# MegaBotv2.net
KiCad netlist of a schematic drawn in EAGLE
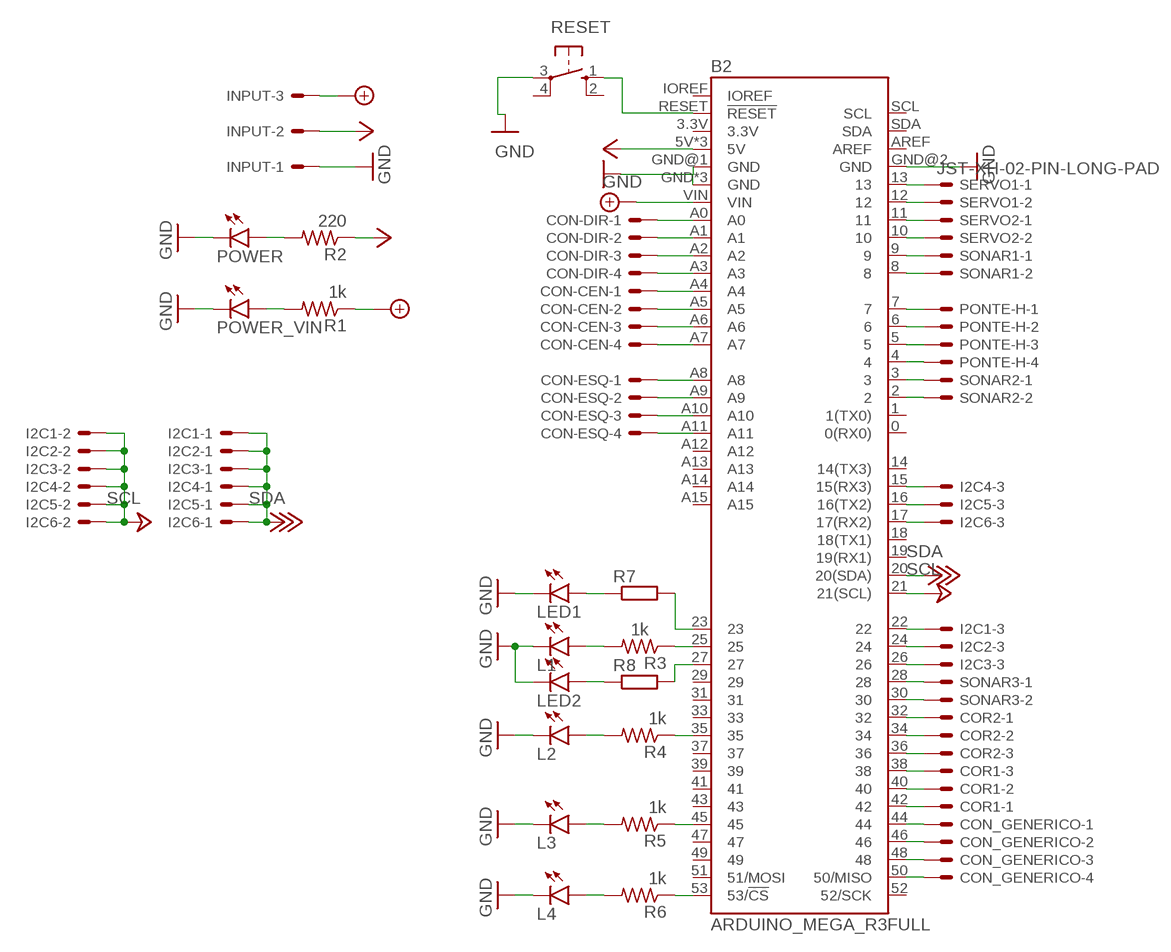
[diagram p0: schematic, sheet 1]

(export (version "E")
  (design (tool "Eeschema 10.0.6"))
  (components
    (comp (ref "B2")
      (value "ARDUINO_MEGA_R3FULL")
      (footprint "eagle-import:ARDUINO_MEGA_NO_SILK")
      (libsource (lib "eagle-import") (part "ARDUINO_MEGA_R3FULL"))
    )
    (comp (ref "CON-CEN")
      (value "JST-XH-04-PIN-LONG-PAD")
      (footprint "eagle-import:JST-XH-04-PACKAGE-LONG-PAD")
      (libsource (lib "eagle-import") (part "JST-XH-04-PIN-LONG-PAD"))
    )
    (comp (ref "CON-DIR")
      (value "JST-XH-04-PIN-LONG-PAD")
      (footprint "eagle-import:JST-XH-04-PACKAGE-LONG-PAD")
      (libsource (lib "eagle-import") (part "JST-XH-04-PIN-LONG-PAD"))
    )
    (comp (ref "CON-ESQ")
      (value "JST-XH-04-PIN-LONG-PAD")
      (footprint "eagle-import:JST-XH-04-PACKAGE-LONG-PAD")
      (libsource (lib "eagle-import") (part "JST-XH-04-PIN-LONG-PAD"))
    )
    (comp (ref "CON_GENERICO")
      (value "JST-XH-04-PIN-LONG-PAD")
      (footprint "eagle-import:JST-XH-04-PACKAGE-LONG-PAD")
      (libsource (lib "eagle-import") (part "JST-XH-04-PIN-LONG-PAD"))
    )
    (comp (ref "COR1")
      (value "JST-XH-03-PIN-LONG-PAD")
      (footprint "eagle-import:JST-XH-03-PACKAGE-LONG-PAD")
      (libsource (lib "eagle-import") (part "JST-XH-03-PIN-LONG-PAD"))
    )
    (comp (ref "COR2")
      (value "JST-XH-03-PIN-LONG-PAD")
      (footprint "eagle-import:JST-XH-03-PACKAGE-LONG-PAD")
      (libsource (lib "eagle-import") (part "JST-XH-03-PIN-LONG-PAD"))
    )
    (comp (ref "I2C1")
      (value "JST-XH-03-PIN-LONG-PAD")
      (footprint "eagle-import:JST-XH-03-PACKAGE-LONG-PAD")
      (libsource (lib "eagle-import") (part "JST-XH-03-PIN-LONG-PAD"))
    )
    (comp (ref "I2C2")
      (value "JST-XH-03-PIN-LONG-PAD")
      (footprint "eagle-import:JST-XH-03-PACKAGE-LONG-PAD")
      (libsource (lib "eagle-import") (part "JST-XH-03-PIN-LONG-PAD"))
    )
    (comp (ref "I2C3")
      (value "JST-XH-03-PIN-LONG-PAD")
      (footprint "eagle-import:JST-XH-03-PACKAGE-LONG-PAD")
      (libsource (lib "eagle-import") (part "JST-XH-03-PIN-LONG-PAD"))
    )
    (comp (ref "I2C4")
      (value "JST-XH-03-PIN-LONG-PAD")
      (footprint "eagle-import:JST-XH-03-PACKAGE-LONG-PAD")
      (libsource (lib "eagle-import") (part "JST-XH-03-PIN-LONG-PAD"))
    )
    (comp (ref "I2C5")
      (value "JST-XH-03-PIN-LONG-PAD")
      (footprint "eagle-import:JST-XH-03-PACKAGE-LONG-PAD")
      (libsource (lib "eagle-import") (part "JST-XH-03-PIN-LONG-PAD"))
    )
    (comp (ref "I2C6")
      (value "JST-XH-03-PIN-LONG-PAD")
      (footprint "eagle-import:JST-XH-03-PACKAGE-LONG-PAD")
      (libsource (lib "eagle-import") (part "JST-XH-03-PIN-LONG-PAD"))
    )
    (comp (ref "INPUT")
      (value "KK-156-3")
      (footprint "eagle-import:KK-156-3")
      (fields (field (name "MF") "MOLEX"))
      (libsource (lib "eagle-import") (part "KK-156-3"))
    )
    (comp (ref "L1")
      (value "LEDLED5MM_LONG_PAD")
      (footprint "eagle-import:LED5MM_LONG_PAD")
      (libsource (lib "eagle-import") (part "LEDLED5MM_LONG_PAD"))
    )
    (comp (ref "L2")
      (value "LEDLED5MM_LONG_PAD")
      (footprint "eagle-import:LED5MM_LONG_PAD")
      (libsource (lib "eagle-import") (part "LEDLED5MM_LONG_PAD"))
    )
    (comp (ref "L3")
      (value "LEDLED5MM_LONG_PAD")
      (footprint "eagle-import:LED5MM_LONG_PAD")
      (libsource (lib "eagle-import") (part "LEDLED5MM_LONG_PAD"))
    )
    (comp (ref "L4")
      (value "LEDLED5MM_LONG_PAD")
      (footprint "eagle-import:LED5MM_LONG_PAD")
      (libsource (lib "eagle-import") (part "LEDLED5MM_LONG_PAD"))
    )
    (comp (ref "LED1")
      (value "LEDKA-3528ASYC")
      (footprint "eagle-import:KA-3528ASYC")
      (libsource (lib "eagle-import") (part "LEDKA-3528ASYC"))
    )
    (comp (ref "LED2")
      (value "LEDKA-3528ASYC")
      (footprint "eagle-import:KA-3528ASYC")
      (libsource (lib "eagle-import") (part "LEDKA-3528ASYC"))
    )
    (comp (ref "PONTE-H")
      (value "JST-XH-04-PIN-LONG-PAD")
      (footprint "eagle-import:JST-XH-04-PACKAGE-LONG-PAD")
      (libsource (lib "eagle-import") (part "JST-XH-04-PIN-LONG-PAD"))
    )
    (comp (ref "POWER")
      (value "LEDLED5MM_LONG_PAD")
      (footprint "eagle-import:LED5MM_LONG_PAD")
      (libsource (lib "eagle-import") (part "LEDLED5MM_LONG_PAD"))
    )
    (comp (ref "POWER_VIN")
      (value "LEDLED5MM_LONG_PAD")
      (footprint "eagle-import:LED5MM_LONG_PAD")
      (libsource (lib "eagle-import") (part "LEDLED5MM_LONG_PAD"))
    )
    (comp (ref "R1")
      (value "1k")
      (footprint "eagle-import:0204_7")
      (libsource (lib "eagle-import") (part "R-US_0204/7"))
    )
    (comp (ref "R2")
      (value "220")
      (footprint "eagle-import:0204_7")
      (libsource (lib "eagle-import") (part "R-US_0204/7"))
    )
    (comp (ref "R3")
      (value "1k")
      (footprint "eagle-import:0204_7")
      (libsource (lib "eagle-import") (part "R-US_0204/7"))
    )
    (comp (ref "R4")
      (value "1k")
      (footprint "eagle-import:0204_7")
      (libsource (lib "eagle-import") (part "R-US_0204/7"))
    )
    (comp (ref "R5")
      (value "1k")
      (footprint "eagle-import:0204_7")
      (libsource (lib "eagle-import") (part "R-US_0204/7"))
    )
    (comp (ref "R6")
      (value "1k")
      (footprint "eagle-import:0204_7")
      (libsource (lib "eagle-import") (part "R-US_0204/7"))
    )
    (comp (ref "R7")
      (value "R-EU_M0805")
      (footprint "eagle-import:M0805")
      (libsource (lib "eagle-import") (part "R-EU_M0805"))
    )
    (comp (ref "R8")
      (value "R-EU_M0805")
      (footprint "eagle-import:M0805")
      (libsource (lib "eagle-import") (part "R-EU_M0805"))
    )
    (comp (ref "RESET")
      (value "10-XX")
      (footprint "eagle-import:B3F-10XX")
      (fields (field (name "MPN") "B3F-1000"))
      (libsource (lib "eagle-import") (part "10-XX"))
    )
    (comp (ref "SERVO1")
      (value "JST-XH-02-PIN-LONG-PAD")
      (footprint "eagle-import:JST-XH-02-PACKAGE-LONG-PAD")
      (libsource (lib "eagle-import") (part "JST-XH-02-PIN-LONG-PAD"))
    )
    (comp (ref "SERVO2")
      (value "JST-XH-02-PIN-LONG-PAD")
      (footprint "eagle-import:JST-XH-02-PACKAGE-LONG-PAD")
      (libsource (lib "eagle-import") (part "JST-XH-02-PIN-LONG-PAD"))
    )
    (comp (ref "SONAR1")
      (value "JST-XH-02-PIN-LONG-PAD")
      (footprint "eagle-import:JST-XH-02-PACKAGE-LONG-PAD")
      (libsource (lib "eagle-import") (part "JST-XH-02-PIN-LONG-PAD"))
    )
    (comp (ref "SONAR2")
      (value "JST-XH-02-PIN-LONG-PAD")
      (footprint "eagle-import:JST-XH-02-PACKAGE-LONG-PAD")
      (libsource (lib "eagle-import") (part "JST-XH-02-PIN-LONG-PAD"))
    )
    (comp (ref "SONAR3")
      (value "JST-XH-02-PIN-LONG-PAD")
      (footprint "eagle-import:JST-XH-02-PACKAGE-LONG-PAD")
      (libsource (lib "eagle-import") (part "JST-XH-02-PIN-LONG-PAD"))
    )
  )
  (nets
    (net (code "1") (name "+8V") (class "Default")
      (node (ref "B2") (pin "VIN") (pinfunction "VIN_VIN") (pintype "bidirectional"))
      (node (ref "INPUT") (pin "3") (pinfunction "S_3") (pintype "passive"))
      (node (ref "R1") (pin "1") (pinfunction "1_1") (pintype "passive"))
    )
    (net (code "2") (name "GND") (class "Default")
      (node (ref "B2") (pin "GND") (pinfunction "GND_GND") (pintype "bidirectional"))
      (node (ref "B2") (pin "GND@1") (pinfunction "GND_GND@1") (pintype "bidirectional"))
      (node (ref "B2") (pin "GND@2") (pinfunction "GND_GND@2") (pintype "bidirectional"))
      (node (ref "B2") (pin "GND@3") (pinfunction "GND_GND@3") (pintype "bidirectional"))
      (node (ref "B2") (pin "GND@4") (pinfunction "GND_GND@4") (pintype "bidirectional"))
      (node (ref "INPUT") (pin "1") (pinfunction "S_1") (pintype "passive"))
      (node (ref "L1") (pin "K") (pinfunction "C_K") (pintype "passive"))
      (node (ref "L2") (pin "K") (pinfunction "C_K") (pintype "passive"))
      (node (ref "L3") (pin "K") (pinfunction "C_K") (pintype "passive"))
      (node (ref "L4") (pin "K") (pinfunction "C_K") (pintype "passive"))
      (node (ref "LED1") (pin "C") (pinfunction "C_C") (pintype "passive"))
      (node (ref "LED2") (pin "C") (pinfunction "C_C") (pintype "passive"))
      (node (ref "POWER") (pin "K") (pinfunction "C_K") (pintype "passive"))
      (node (ref "POWER_VIN") (pin "K") (pinfunction "C_K") (pintype "passive"))
      (node (ref "RESET") (pin "3") (pinfunction "P_3") (pintype "passive"))
    )
    (net (code "3") (name "Net-(B2-15(RX3))") (class "Default")
      (node (ref "B2") (pin "15") (pinfunction "15(RX3)_15") (pintype "bidirectional"))
      (node (ref "I2C4") (pin "3") (pinfunction "S_3") (pintype "passive"))
    )
    (net (code "4") (name "Net-(B2-16(TX2))") (class "Default")
      (node (ref "B2") (pin "16") (pinfunction "16(TX2)_16") (pintype "bidirectional"))
      (node (ref "I2C5") (pin "3") (pinfunction "S_3") (pintype "passive"))
    )
    (net (code "5") (name "Net-(B2-17(RX2))") (class "Default")
      (node (ref "B2") (pin "17") (pinfunction "17(RX2)_17") (pintype "bidirectional"))
      (node (ref "I2C6") (pin "3") (pinfunction "S_3") (pintype "passive"))
    )
    (net (code "6") (name "Net-(B2-50{slash}MISO)") (class "Default")
      (node (ref "B2") (pin "50") (pinfunction "50/MISO_50") (pintype "bidirectional"))
      (node (ref "CON_GENERICO") (pin "4") (pinfunction "S_4") (pintype "passive"))
    )
    (net (code "7") (name "Net-(B2-53{slash}~{CS})") (class "Default")
      (node (ref "B2") (pin "53") (pinfunction "53/~{CS}_53") (pintype "bidirectional"))
      (node (ref "R6") (pin "1") (pinfunction "1_1") (pintype "passive"))
    )
    (net (code "8") (name "Net-(B2-Pad23)") (class "Default")
      (node (ref "B2") (pin "23") (pinfunction "23_23") (pintype "bidirectional"))
      (node (ref "R7") (pin "2") (pinfunction "2_2") (pintype "passive"))
    )
    (net (code "9") (name "Net-(B2-Pad25)") (class "Default")
      (node (ref "B2") (pin "25") (pinfunction "25_25") (pintype "bidirectional"))
      (node (ref "R3") (pin "1") (pinfunction "1_1") (pintype "passive"))
    )
    (net (code "10") (name "Net-(B2-Pad27)") (class "Default")
      (node (ref "B2") (pin "27") (pinfunction "27_27") (pintype "bidirectional"))
      (node (ref "R8") (pin "2") (pinfunction "2_2") (pintype "passive"))
    )
    (net (code "11") (name "Net-(B2-Pad35)") (class "Default")
      (node (ref "B2") (pin "35") (pinfunction "35_35") (pintype "bidirectional"))
      (node (ref "R4") (pin "1") (pinfunction "1_1") (pintype "passive"))
    )
    (net (code "12") (name "Net-(B2-Pad45)") (class "Default")
      (node (ref "B2") (pin "45") (pinfunction "45_45") (pintype "bidirectional"))
      (node (ref "R5") (pin "1") (pinfunction "1_1") (pintype "passive"))
    )
    (net (code "13") (name "Net-(B2-~{RESET})") (class "Default")
      (node (ref "B2") (pin "RESET") (pinfunction "~{RESET}_RESET") (pintype "bidirectional"))
      (node (ref "RESET") (pin "1") (pinfunction "S_1") (pintype "passive"))
    )
    (net (code "14") (name "Net-(CON-CENA-S)") (class "Default")
      (node (ref "B2") (pin "A4") (pinfunction "A4_A4") (pintype "bidirectional"))
      (node (ref "CON-CEN") (pin "1") (pinfunction "S_1") (pintype "passive"))
    )
    (net (code "15") (name "Net-(CON-CENB-S)") (class "Default")
      (node (ref "B2") (pin "A5") (pinfunction "A5_A5") (pintype "bidirectional"))
      (node (ref "CON-CEN") (pin "2") (pinfunction "S_2") (pintype "passive"))
    )
    (net (code "16") (name "Net-(CON-CENC-S)") (class "Default")
      (node (ref "B2") (pin "A6") (pinfunction "A6_A6") (pintype "bidirectional"))
      (node (ref "CON-CEN") (pin "3") (pinfunction "S_3") (pintype "passive"))
    )
    (net (code "17") (name "Net-(CON-CEND-S)") (class "Default")
      (node (ref "B2") (pin "A7") (pinfunction "A7_A7") (pintype "bidirectional"))
      (node (ref "CON-CEN") (pin "4") (pinfunction "S_4") (pintype "passive"))
    )
    (net (code "18") (name "Net-(CON-DIRA-S)") (class "Default")
      (node (ref "B2") (pin "A0") (pinfunction "A0_A0") (pintype "bidirectional"))
      (node (ref "CON-DIR") (pin "1") (pinfunction "S_1") (pintype "passive"))
    )
    (net (code "19") (name "Net-(CON-DIRB-S)") (class "Default")
      (node (ref "B2") (pin "A1") (pinfunction "A1_A1") (pintype "bidirectional"))
      (node (ref "CON-DIR") (pin "2") (pinfunction "S_2") (pintype "passive"))
    )
    (net (code "20") (name "Net-(CON-DIRC-S)") (class "Default")
      (node (ref "B2") (pin "A2") (pinfunction "A2_A2") (pintype "bidirectional"))
      (node (ref "CON-DIR") (pin "3") (pinfunction "S_3") (pintype "passive"))
    )
    (net (code "21") (name "Net-(CON-DIRD-S)") (class "Default")
      (node (ref "B2") (pin "A3") (pinfunction "A3_A3") (pintype "bidirectional"))
      (node (ref "CON-DIR") (pin "4") (pinfunction "S_4") (pintype "passive"))
    )
    (net (code "22") (name "Net-(CON-ESQA-S)") (class "Default")
      (node (ref "B2") (pin "A8") (pinfunction "A8_A8") (pintype "bidirectional"))
      (node (ref "CON-ESQ") (pin "1") (pinfunction "S_1") (pintype "passive"))
    )
    (net (code "23") (name "Net-(CON-ESQB-S)") (class "Default")
      (node (ref "B2") (pin "A9") (pinfunction "A9_A9") (pintype "bidirectional"))
      (node (ref "CON-ESQ") (pin "2") (pinfunction "S_2") (pintype "passive"))
    )
    (net (code "24") (name "Net-(CON-ESQC-S)") (class "Default")
      (node (ref "B2") (pin "A10") (pinfunction "A10_A10") (pintype "bidirectional"))
      (node (ref "CON-ESQ") (pin "3") (pinfunction "S_3") (pintype "passive"))
    )
    (net (code "25") (name "Net-(CON-ESQD-S)") (class "Default")
      (node (ref "B2") (pin "A11") (pinfunction "A11_A11") (pintype "bidirectional"))
      (node (ref "CON-ESQ") (pin "4") (pinfunction "S_4") (pintype "passive"))
    )
    (net (code "26") (name "Net-(CON_GENERICOA-S)") (class "Default")
      (node (ref "B2") (pin "44") (pinfunction "44_44") (pintype "bidirectional"))
      (node (ref "CON_GENERICO") (pin "1") (pinfunction "S_1") (pintype "passive"))
    )
    (net (code "27") (name "Net-(CON_GENERICOB-S)") (class "Default")
      (node (ref "B2") (pin "46") (pinfunction "46_46") (pintype "bidirectional"))
      (node (ref "CON_GENERICO") (pin "2") (pinfunction "S_2") (pintype "passive"))
    )
    (net (code "28") (name "Net-(CON_GENERICOC-S)") (class "Default")
      (node (ref "B2") (pin "48") (pinfunction "48_48") (pintype "bidirectional"))
      (node (ref "CON_GENERICO") (pin "3") (pinfunction "S_3") (pintype "passive"))
    )
    (net (code "29") (name "Net-(COR1A-S)") (class "Default")
      (node (ref "B2") (pin "42") (pinfunction "42_42") (pintype "bidirectional"))
      (node (ref "COR1") (pin "1") (pinfunction "S_1") (pintype "passive"))
    )
    (net (code "30") (name "Net-(COR1B-S)") (class "Default")
      (node (ref "B2") (pin "40") (pinfunction "40_40") (pintype "bidirectional"))
      (node (ref "COR1") (pin "2") (pinfunction "S_2") (pintype "passive"))
    )
    (net (code "31") (name "Net-(COR1C-S)") (class "Default")
      (node (ref "B2") (pin "38") (pinfunction "38_38") (pintype "bidirectional"))
      (node (ref "COR1") (pin "3") (pinfunction "S_3") (pintype "passive"))
    )
    (net (code "32") (name "Net-(COR2A-S)") (class "Default")
      (node (ref "B2") (pin "32") (pinfunction "32_32") (pintype "bidirectional"))
      (node (ref "COR2") (pin "1") (pinfunction "S_1") (pintype "passive"))
    )
    (net (code "33") (name "Net-(COR2B-S)") (class "Default")
      (node (ref "B2") (pin "34") (pinfunction "34_34") (pintype "bidirectional"))
      (node (ref "COR2") (pin "2") (pinfunction "S_2") (pintype "passive"))
    )
    (net (code "34") (name "Net-(COR2C-S)") (class "Default")
      (node (ref "B2") (pin "36") (pinfunction "36_36") (pintype "bidirectional"))
      (node (ref "COR2") (pin "3") (pinfunction "S_3") (pintype "passive"))
    )
    (net (code "35") (name "Net-(I2C1C-S)") (class "Default")
      (node (ref "B2") (pin "22") (pinfunction "22_22") (pintype "bidirectional"))
      (node (ref "I2C1") (pin "3") (pinfunction "S_3") (pintype "passive"))
    )
    (net (code "36") (name "Net-(I2C2C-S)") (class "Default")
      (node (ref "B2") (pin "24") (pinfunction "24_24") (pintype "bidirectional"))
      (node (ref "I2C2") (pin "3") (pinfunction "S_3") (pintype "passive"))
    )
    (net (code "37") (name "Net-(I2C3C-S)") (class "Default")
      (node (ref "B2") (pin "26") (pinfunction "26_26") (pintype "bidirectional"))
      (node (ref "I2C3") (pin "3") (pinfunction "S_3") (pintype "passive"))
    )
    (net (code "38") (name "Net-(L1-PadA)") (class "Default")
      (node (ref "L1") (pin "A") (pinfunction "A_A") (pintype "passive"))
      (node (ref "R3") (pin "2") (pinfunction "2_2") (pintype "passive"))
    )
    (net (code "39") (name "Net-(L2-PadA)") (class "Default")
      (node (ref "L2") (pin "A") (pinfunction "A_A") (pintype "passive"))
      (node (ref "R4") (pin "2") (pinfunction "2_2") (pintype "passive"))
    )
    (net (code "40") (name "Net-(L3-PadA)") (class "Default")
      (node (ref "L3") (pin "A") (pinfunction "A_A") (pintype "passive"))
      (node (ref "R5") (pin "2") (pinfunction "2_2") (pintype "passive"))
    )
    (net (code "41") (name "Net-(L4-PadA)") (class "Default")
      (node (ref "L4") (pin "A") (pinfunction "A_A") (pintype "passive"))
      (node (ref "R6") (pin "2") (pinfunction "2_2") (pintype "passive"))
    )
    (net (code "42") (name "Net-(LED1-PadA)") (class "Default")
      (node (ref "LED1") (pin "A") (pinfunction "A_A") (pintype "passive"))
      (node (ref "R7") (pin "1") (pinfunction "1_1") (pintype "passive"))
    )
    (net (code "43") (name "Net-(LED2-PadA)") (class "Default")
      (node (ref "LED2") (pin "A") (pinfunction "A_A") (pintype "passive"))
      (node (ref "R8") (pin "1") (pinfunction "1_1") (pintype "passive"))
    )
    (net (code "44") (name "Net-(PONTE-HA-S)") (class "Default")
      (node (ref "B2") (pin "7") (pinfunction "7_7") (pintype "bidirectional"))
      (node (ref "PONTE-H") (pin "1") (pinfunction "S_1") (pintype "passive"))
    )
    (net (code "45") (name "Net-(PONTE-HB-S)") (class "Default")
      (node (ref "B2") (pin "6") (pinfunction "6_6") (pintype "bidirectional"))
      (node (ref "PONTE-H") (pin "2") (pinfunction "S_2") (pintype "passive"))
    )
    (net (code "46") (name "Net-(PONTE-HC-S)") (class "Default")
      (node (ref "B2") (pin "5") (pinfunction "5_5") (pintype "bidirectional"))
      (node (ref "PONTE-H") (pin "3") (pinfunction "S_3") (pintype "passive"))
    )
    (net (code "47") (name "Net-(PONTE-HD-S)") (class "Default")
      (node (ref "B2") (pin "4") (pinfunction "4_4") (pintype "bidirectional"))
      (node (ref "PONTE-H") (pin "4") (pinfunction "S_4") (pintype "passive"))
    )
    (net (code "48") (name "Net-(POWER-PadA)") (class "Default")
      (node (ref "POWER") (pin "A") (pinfunction "A_A") (pintype "passive"))
      (node (ref "R2") (pin "2") (pinfunction "2_2") (pintype "passive"))
    )
    (net (code "49") (name "Net-(POWER_VIN-PadA)") (class "Default")
      (node (ref "POWER_VIN") (pin "A") (pinfunction "A_A") (pintype "passive"))
      (node (ref "R1") (pin "2") (pinfunction "2_2") (pintype "passive"))
    )
    (net (code "50") (name "Net-(SERVO1A-S)") (class "Default")
      (node (ref "B2") (pin "13") (pinfunction "13_13") (pintype "bidirectional"))
      (node (ref "SERVO1") (pin "1") (pinfunction "S_1") (pintype "passive"))
    )
    (net (code "51") (name "Net-(SERVO1B-S)") (class "Default")
      (node (ref "B2") (pin "12") (pinfunction "12_12") (pintype "bidirectional"))
      (node (ref "SERVO1") (pin "2") (pinfunction "S_2") (pintype "passive"))
    )
    (net (code "52") (name "Net-(SERVO2A-S)") (class "Default")
      (node (ref "B2") (pin "11") (pinfunction "11_11") (pintype "bidirectional"))
      (node (ref "SERVO2") (pin "1") (pinfunction "S_1") (pintype "passive"))
    )
    (net (code "53") (name "Net-(SERVO2B-S)") (class "Default")
      (node (ref "B2") (pin "10") (pinfunction "10_10") (pintype "bidirectional"))
      (node (ref "SERVO2") (pin "2") (pinfunction "S_2") (pintype "passive"))
    )
    (net (code "54") (name "Net-(SONAR1A-S)") (class "Default")
      (node (ref "B2") (pin "9") (pinfunction "9_9") (pintype "bidirectional"))
      (node (ref "SONAR1") (pin "1") (pinfunction "S_1") (pintype "passive"))
    )
    (net (code "55") (name "Net-(SONAR1B-S)") (class "Default")
      (node (ref "B2") (pin "8") (pinfunction "8_8") (pintype "bidirectional"))
      (node (ref "SONAR1") (pin "2") (pinfunction "S_2") (pintype "passive"))
    )
    (net (code "56") (name "Net-(SONAR2A-S)") (class "Default")
      (node (ref "B2") (pin "3") (pinfunction "3_3") (pintype "bidirectional"))
      (node (ref "SONAR2") (pin "1") (pinfunction "S_1") (pintype "passive"))
    )
    (net (code "57") (name "Net-(SONAR2B-S)") (class "Default")
      (node (ref "B2") (pin "2") (pinfunction "2_2") (pintype "bidirectional"))
      (node (ref "SONAR2") (pin "2") (pinfunction "S_2") (pintype "passive"))
    )
    (net (code "58") (name "Net-(SONAR3A-S)") (class "Default")
      (node (ref "B2") (pin "28") (pinfunction "28_28") (pintype "bidirectional"))
      (node (ref "SONAR3") (pin "1") (pinfunction "S_1") (pintype "passive"))
    )
    (net (code "59") (name "Net-(SONAR3B-S)") (class "Default")
      (node (ref "B2") (pin "30") (pinfunction "30_30") (pintype "bidirectional"))
      (node (ref "SONAR3") (pin "2") (pinfunction "S_2") (pintype "passive"))
    )
    (net (code "60") (name "SCL") (class "Default")
      (node (ref "B2") (pin "21") (pinfunction "21(SCL)_21") (pintype "bidirectional"))
      (node (ref "I2C1") (pin "2") (pinfunction "S_2") (pintype "passive"))
      (node (ref "I2C2") (pin "2") (pinfunction "S_2") (pintype "passive"))
      (node (ref "I2C3") (pin "2") (pinfunction "S_2") (pintype "passive"))
      (node (ref "I2C4") (pin "2") (pinfunction "S_2") (pintype "passive"))
      (node (ref "I2C5") (pin "2") (pinfunction "S_2") (pintype "passive"))
      (node (ref "I2C6") (pin "2") (pinfunction "S_2") (pintype "passive"))
    )
    (net (code "61") (name "SDA") (class "Default")
      (node (ref "B2") (pin "20") (pinfunction "20(SDA)_20") (pintype "bidirectional"))
      (node (ref "I2C1") (pin "1") (pinfunction "S_1") (pintype "passive"))
      (node (ref "I2C2") (pin "1") (pinfunction "S_1") (pintype "passive"))
      (node (ref "I2C3") (pin "1") (pinfunction "S_1") (pintype "passive"))
      (node (ref "I2C4") (pin "1") (pinfunction "S_1") (pintype "passive"))
      (node (ref "I2C5") (pin "1") (pinfunction "S_1") (pintype "passive"))
      (node (ref "I2C6") (pin "1") (pinfunction "S_1") (pintype "passive"))
    )
    (net (code "62") (name "VCC") (class "Default")
      (node (ref "B2") (pin "5V") (pinfunction "5V_5V") (pintype "bidirectional"))
      (node (ref "B2") (pin "5V@1") (pinfunction "5V_5V@1") (pintype "bidirectional"))
      (node (ref "B2") (pin "5V@2") (pinfunction "5V_5V@2") (pintype "bidirectional"))
      (node (ref "INPUT") (pin "2") (pinfunction "S_2") (pintype "passive"))
      (node (ref "R2") (pin "1") (pinfunction "1_1") (pintype "passive"))
    )
    (net (code "63") (name "unconnected-(B2-0(RX0)-Pad0)") (class "Default")
      (node (ref "B2") (pin "0") (pinfunction "0(RX0)_0") (pintype "bidirectional"))
    )
    (net (code "64") (name "unconnected-(B2-1(TX0)-Pad1)") (class "Default")
      (node (ref "B2") (pin "1") (pinfunction "1(TX0)_1") (pintype "bidirectional"))
    )
    (net (code "65") (name "unconnected-(B2-14(TX3)-Pad14)") (class "Default")
      (node (ref "B2") (pin "14") (pinfunction "14(TX3)_14") (pintype "bidirectional"))
    )
    (net (code "66") (name "unconnected-(B2-18(TX1)-Pad18)") (class "Default")
      (node (ref "B2") (pin "18") (pinfunction "18(TX1)_18") (pintype "bidirectional"))
    )
    (net (code "67") (name "unconnected-(B2-19(RX1)-Pad19)") (class "Default")
      (node (ref "B2") (pin "19") (pinfunction "19(RX1)_19") (pintype "bidirectional"))
    )
    (net (code "68") (name "unconnected-(B2-51{slash}MOSI-Pad51)") (class "Default")
      (node (ref "B2") (pin "51") (pinfunction "51/MOSI_51") (pintype "bidirectional"))
    )
    (net (code "69") (name "unconnected-(B2-52{slash}SCK-Pad52)") (class "Default")
      (node (ref "B2") (pin "52") (pinfunction "52/SCK_52") (pintype "bidirectional"))
    )
    (net (code "70") (name "unconnected-(B2-Pad3.3V)") (class "Default")
      (node (ref "B2") (pin "3.3V") (pinfunction "3.3V_3.3V") (pintype "bidirectional"))
    )
    (net (code "71") (name "unconnected-(B2-Pad29)") (class "Default")
      (node (ref "B2") (pin "29") (pinfunction "29_29") (pintype "bidirectional"))
    )
    (net (code "72") (name "unconnected-(B2-Pad31)") (class "Default")
      (node (ref "B2") (pin "31") (pinfunction "31_31") (pintype "bidirectional"))
    )
    (net (code "73") (name "unconnected-(B2-Pad33)") (class "Default")
      (node (ref "B2") (pin "33") (pinfunction "33_33") (pintype "bidirectional"))
    )
    (net (code "74") (name "unconnected-(B2-Pad37)") (class "Default")
      (node (ref "B2") (pin "37") (pinfunction "37_37") (pintype "bidirectional"))
    )
    (net (code "75") (name "unconnected-(B2-Pad39)") (class "Default")
      (node (ref "B2") (pin "39") (pinfunction "39_39") (pintype "bidirectional"))
    )
    (net (code "76") (name "unconnected-(B2-Pad41)") (class "Default")
      (node (ref "B2") (pin "41") (pinfunction "41_41") (pintype "bidirectional"))
    )
    (net (code "77") (name "unconnected-(B2-Pad43)") (class "Default")
      (node (ref "B2") (pin "43") (pinfunction "43_43") (pintype "bidirectional"))
    )
    (net (code "78") (name "unconnected-(B2-Pad47)") (class "Default")
      (node (ref "B2") (pin "47") (pinfunction "47_47") (pintype "bidirectional"))
    )
    (net (code "79") (name "unconnected-(B2-Pad49)") (class "Default")
      (node (ref "B2") (pin "49") (pinfunction "49_49") (pintype "bidirectional"))
    )
    (net (code "80") (name "unconnected-(B2-PadA12)") (class "Default")
      (node (ref "B2") (pin "A12") (pinfunction "A12_A12") (pintype "bidirectional"))
    )
    (net (code "81") (name "unconnected-(B2-PadA13)") (class "Default")
      (node (ref "B2") (pin "A13") (pinfunction "A13_A13") (pintype "bidirectional"))
    )
    (net (code "82") (name "unconnected-(B2-PadA14)") (class "Default")
      (node (ref "B2") (pin "A14") (pinfunction "A14_A14") (pintype "bidirectional"))
    )
    (net (code "83") (name "unconnected-(B2-PadA15)") (class "Default")
      (node (ref "B2") (pin "A15") (pinfunction "A15_A15") (pintype "bidirectional"))
    )
    (net (code "84") (name "unconnected-(B2-PadAREF)") (class "Default")
      (node (ref "B2") (pin "AREF") (pinfunction "AREF_AREF") (pintype "bidirectional"))
    )
    (net (code "85") (name "unconnected-(B2-PadIOREF)") (class "Default")
      (node (ref "B2") (pin "IOREF") (pinfunction "IOREF_IOREF") (pintype "bidirectional"))
    )
    (net (code "86") (name "unconnected-(B2-PadSCL)") (class "Default")
      (node (ref "B2") (pin "SCL") (pinfunction "SCL_SCL") (pintype "bidirectional"))
    )
    (net (code "87") (name "unconnected-(B2-PadSDA)") (class "Default")
      (node (ref "B2") (pin "SDA") (pinfunction "SDA_SDA") (pintype "bidirectional"))
    )
    (net (code "88") (name "unconnected-(RESET-P1-Pad4)") (class "Default")
      (node (ref "RESET") (pin "4") (pinfunction "P1_4") (pintype "passive"))
    )
    (net (code "89") (name "unconnected-(RESET-S1-Pad2)") (class "Default")
      (node (ref "RESET") (pin "2") (pinfunction "S1_2") (pintype "passive"))
    )
  )
)
